# 3_RK.net
KiCad netlist of a schematic drawn in Altium Designer
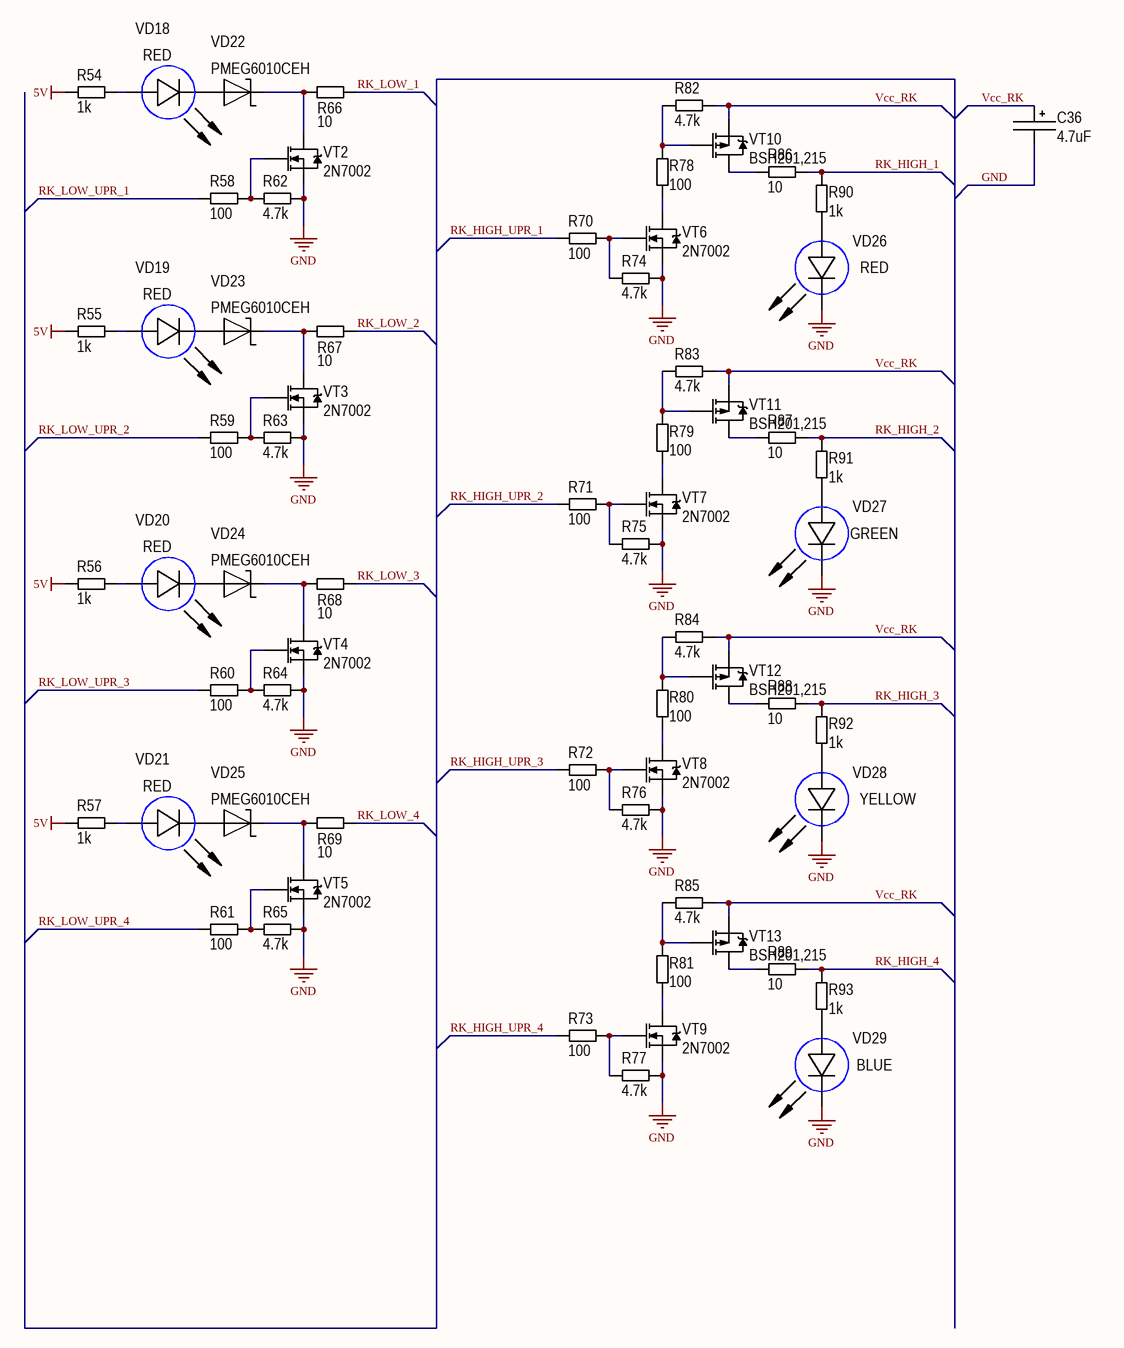
[diagram p0: 3_RK.SchDoc]

(export (version "E")
  (design (tool "Eeschema 10.0.6"))
  (components
    (comp (ref "C36")
      (value "4.7uF")
      (footprint "TANTAL_C")
      (libsource (lib "Condensators") (part "TantalCap"))
    )
    (comp (ref "R54") (value "1k") (footprint "CH0805R") (libsource (lib "Resistors") (part "Resistor")))
    (comp (ref "R55") (value "1k") (footprint "CH0805R") (libsource (lib "Resistors") (part "Resistor")))
    (comp (ref "R56") (value "1k") (footprint "CH0805R") (libsource (lib "Resistors") (part "Resistor")))
    (comp (ref "R57") (value "1k") (footprint "CH0805R") (libsource (lib "Resistors") (part "Resistor")))
    (comp (ref "R58") (value "100") (footprint "CH0603R") (libsource (lib "Resistors") (part "Resistor")))
    (comp (ref "R59") (value "100") (footprint "CH0603R") (libsource (lib "Resistors") (part "Resistor")))
    (comp (ref "R60") (value "100") (footprint "CH0603R") (libsource (lib "Resistors") (part "Resistor")))
    (comp (ref "R61") (value "100") (footprint "CH0603R") (libsource (lib "Resistors") (part "Resistor")))
    (comp (ref "R62") (value "4.7k") (footprint "CH0603R") (libsource (lib "Resistors") (part "Resistor")))
    (comp (ref "R63") (value "4.7k") (footprint "CH0603R") (libsource (lib "Resistors") (part "Resistor")))
    (comp (ref "R64") (value "4.7k") (footprint "CH0603R") (libsource (lib "Resistors") (part "Resistor")))
    (comp (ref "R65") (value "4.7k") (footprint "CH0603R") (libsource (lib "Resistors") (part "Resistor")))
    (comp (ref "R66") (value "10") (footprint "CH0603R") (libsource (lib "Resistors") (part "Resistor")))
    (comp (ref "R67") (value "10") (footprint "CH0603R") (libsource (lib "Resistors") (part "Resistor")))
    (comp (ref "R68") (value "10") (footprint "CH0603R") (libsource (lib "Resistors") (part "Resistor")))
    (comp (ref "R69") (value "10") (footprint "CH0603R") (libsource (lib "Resistors") (part "Resistor")))
    (comp (ref "R70") (value "100") (footprint "CH0603R") (libsource (lib "Resistors") (part "Resistor")))
    (comp (ref "R71") (value "100") (footprint "CH0603R") (libsource (lib "Resistors") (part "Resistor")))
    (comp (ref "R72") (value "100") (footprint "CH0603R") (libsource (lib "Resistors") (part "Resistor")))
    (comp (ref "R73") (value "100") (footprint "CH0603R") (libsource (lib "Resistors") (part "Resistor")))
    (comp (ref "R74") (value "4.7k") (footprint "CH0603R") (libsource (lib "Resistors") (part "Resistor")))
    (comp (ref "R75") (value "4.7k") (footprint "CH0603R") (libsource (lib "Resistors") (part "Resistor")))
    (comp (ref "R76") (value "4.7k") (footprint "CH0603R") (libsource (lib "Resistors") (part "Resistor")))
    (comp (ref "R77") (value "4.7k") (footprint "CH0603R") (libsource (lib "Resistors") (part "Resistor")))
    (comp (ref "R78") (value "100") (footprint "CH0603R") (libsource (lib "Resistors") (part "Resistor")))
    (comp (ref "R79") (value "100") (footprint "CH0603R") (libsource (lib "Resistors") (part "Resistor")))
    (comp (ref "R80") (value "100") (footprint "CH0603R") (libsource (lib "Resistors") (part "Resistor")))
    (comp (ref "R81") (value "100") (footprint "CH0603R") (libsource (lib "Resistors") (part "Resistor")))
    (comp (ref "R82") (value "4.7k") (footprint "CH0603R") (libsource (lib "Resistors") (part "Resistor")))
    (comp (ref "R83") (value "4.7k") (footprint "CH0603R") (libsource (lib "Resistors") (part "Resistor")))
    (comp (ref "R84") (value "4.7k") (footprint "CH0603R") (libsource (lib "Resistors") (part "Resistor")))
    (comp (ref "R85") (value "4.7k") (footprint "CH0603R") (libsource (lib "Resistors") (part "Resistor")))
    (comp (ref "R86") (value "10") (footprint "CH0603R") (libsource (lib "Resistors") (part "Resistor")))
    (comp (ref "R87") (value "10") (footprint "CH0603R") (libsource (lib "Resistors") (part "Resistor")))
    (comp (ref "R88") (value "10") (footprint "CH0603R") (libsource (lib "Resistors") (part "Resistor")))
    (comp (ref "R89") (value "10") (footprint "CH0603R") (libsource (lib "Resistors") (part "Resistor")))
    (comp (ref "R90") (value "1k") (footprint "CH0805R") (libsource (lib "Resistors") (part "Resistor")))
    (comp (ref "R91") (value "1k") (footprint "CH0805R") (libsource (lib "Resistors") (part "Resistor")))
    (comp (ref "R92") (value "1k") (footprint "CH0805R") (libsource (lib "Resistors") (part "Resistor")))
    (comp (ref "R93") (value "1k") (footprint "CH0805R") (libsource (lib "Resistors") (part "Resistor")))
    (comp (ref "VD18") (value "RED") (footprint "CH0603LB") (libsource (lib "Diods") (part "LED_1")))
    (comp (ref "VD19") (value "RED") (footprint "CH0603LB") (libsource (lib "Diods") (part "LED_1")))
    (comp (ref "VD20") (value "RED") (footprint "CH0603LB") (libsource (lib "Diods") (part "LED_1")))
    (comp (ref "VD21") (value "RED") (footprint "CH0603LB") (libsource (lib "Diods") (part "LED_1")))
    (comp (ref "VD22")
      (value "PMEG6010CEH")
      (footprint "SOD123F")
      (libsource (lib "Diods") (part "Diod Schottky"))
    )
    (comp (ref "VD23")
      (value "PMEG6010CEH")
      (footprint "SOD123F")
      (libsource (lib "Diods") (part "Diod Schottky"))
    )
    (comp (ref "VD24")
      (value "PMEG6010CEH")
      (footprint "SOD123F")
      (libsource (lib "Diods") (part "Diod Schottky"))
    )
    (comp (ref "VD25")
      (value "PMEG6010CEH")
      (footprint "SOD123F")
      (libsource (lib "Diods") (part "Diod Schottky"))
    )
    (comp (ref "VD26") (value "RED") (footprint "CH0603LB") (libsource (lib "Diods") (part "LED_1")))
    (comp (ref "VD27") (value "GREEN") (footprint "CH0603LB") (libsource (lib "Diods") (part "LED_1")))
    (comp (ref "VD28") (value "YELLOW") (footprint "CH0603LB") (libsource (lib "Diods") (part "LED_1")))
    (comp (ref "VD29") (value "BLUE") (footprint "CH0603LB") (libsource (lib "Diods") (part "LED_1")))
    (comp (ref "VT2")
      (value "2N7002")
      (footprint "SOT23_123")
      (description "Mosfet")
      (libsource (lib "Tranzistor") (part "N-chanel"))
    )
    (comp (ref "VT3")
      (value "2N7002")
      (footprint "SOT23_123")
      (description "Mosfet")
      (libsource (lib "Tranzistor") (part "N-chanel"))
    )
    (comp (ref "VT4")
      (value "2N7002")
      (footprint "SOT23_123")
      (description "Mosfet")
      (libsource (lib "Tranzistor") (part "N-chanel"))
    )
    (comp (ref "VT5")
      (value "2N7002")
      (footprint "SOT23_123")
      (description "Mosfet")
      (libsource (lib "Tranzistor") (part "N-chanel"))
    )
    (comp (ref "VT6")
      (value "2N7002")
      (footprint "SOT23_123")
      (description "Mosfet")
      (libsource (lib "Tranzistor") (part "N-chanel"))
    )
    (comp (ref "VT7")
      (value "2N7002")
      (footprint "SOT23_123")
      (description "Mosfet")
      (libsource (lib "Tranzistor") (part "N-chanel"))
    )
    (comp (ref "VT8")
      (value "2N7002")
      (footprint "SOT23_123")
      (description "Mosfet")
      (libsource (lib "Tranzistor") (part "N-chanel"))
    )
    (comp (ref "VT9")
      (value "2N7002")
      (footprint "SOT23_123")
      (description "Mosfet")
      (libsource (lib "Tranzistor") (part "N-chanel"))
    )
    (comp (ref "VT10")
      (value "BSH201,215")
      (footprint "SOT23_123")
      (description "Mosfet")
      (libsource (lib "Tranzistor") (part "P-chanel"))
    )
    (comp (ref "VT11")
      (value "BSH201,215")
      (footprint "SOT23_123")
      (description "Mosfet")
      (libsource (lib "Tranzistor") (part "P-chanel"))
    )
    (comp (ref "VT12")
      (value "BSH201,215")
      (footprint "SOT23_123")
      (description "Mosfet")
      (libsource (lib "Tranzistor") (part "P-chanel"))
    )
    (comp (ref "VT13")
      (value "BSH201,215")
      (footprint "SOT23_123")
      (description "Mosfet")
      (libsource (lib "Tranzistor") (part "P-chanel"))
    )
  )
  (nets
    (net (code "1") (name "/RK_HIGH_1") (class "Default")
      (node (ref "R86") (pin "1") (pinfunction "1_1") (pintype "passive"))
      (node (ref "R90") (pin "2") (pinfunction "2_2") (pintype "passive"))
    )
    (net (code "2") (name "/RK_HIGH_2") (class "Default")
      (node (ref "R87") (pin "1") (pinfunction "1_1") (pintype "passive"))
      (node (ref "R91") (pin "2") (pinfunction "2_2") (pintype "passive"))
    )
    (net (code "3") (name "/RK_HIGH_3") (class "Default")
      (node (ref "R88") (pin "1") (pinfunction "1_1") (pintype "passive"))
      (node (ref "R92") (pin "2") (pinfunction "2_2") (pintype "passive"))
    )
    (net (code "4") (name "/RK_HIGH_4") (class "Default")
      (node (ref "R89") (pin "1") (pinfunction "1_1") (pintype "passive"))
      (node (ref "R93") (pin "2") (pinfunction "2_2") (pintype "passive"))
    )
    (net (code "5") (name "/RK_HIGH_UPR_1") (class "Default")
      (node (ref "R70") (pin "2") (pinfunction "2_2") (pintype "passive"))
    )
    (net (code "6") (name "/RK_HIGH_UPR_2") (class "Default")
      (node (ref "R71") (pin "2") (pinfunction "2_2") (pintype "passive"))
    )
    (net (code "7") (name "/RK_HIGH_UPR_3") (class "Default")
      (node (ref "R72") (pin "2") (pinfunction "2_2") (pintype "passive"))
    )
    (net (code "8") (name "/RK_HIGH_UPR_4") (class "Default")
      (node (ref "R73") (pin "2") (pinfunction "2_2") (pintype "passive"))
    )
    (net (code "9") (name "/RK_LOW_1") (class "Default")
      (node (ref "R66") (pin "1") (pinfunction "1_1") (pintype "passive"))
    )
    (net (code "10") (name "/RK_LOW_2") (class "Default")
      (node (ref "R67") (pin "1") (pinfunction "1_1") (pintype "passive"))
    )
    (net (code "11") (name "/RK_LOW_3") (class "Default")
      (node (ref "R68") (pin "1") (pinfunction "1_1") (pintype "passive"))
    )
    (net (code "12") (name "/RK_LOW_4") (class "Default")
      (node (ref "R69") (pin "1") (pinfunction "1_1") (pintype "passive"))
    )
    (net (code "13") (name "/RK_LOW_UPR_1") (class "Default")
      (node (ref "R58") (pin "2") (pinfunction "2_2") (pintype "passive"))
    )
    (net (code "14") (name "/RK_LOW_UPR_2") (class "Default")
      (node (ref "R59") (pin "2") (pinfunction "2_2") (pintype "passive"))
    )
    (net (code "15") (name "/RK_LOW_UPR_3") (class "Default")
      (node (ref "R60") (pin "2") (pinfunction "2_2") (pintype "passive"))
    )
    (net (code "16") (name "/RK_LOW_UPR_4") (class "Default")
      (node (ref "R61") (pin "2") (pinfunction "2_2") (pintype "passive"))
    )
    (net (code "17") (name "/Vcc_RK") (class "Default")
      (node (ref "C36") (pin "1") (pinfunction "1_1") (pintype "power_in"))
      (node (ref "R82") (pin "1") (pinfunction "1_1") (pintype "passive"))
      (node (ref "R83") (pin "1") (pinfunction "1_1") (pintype "passive"))
      (node (ref "R84") (pin "1") (pinfunction "1_1") (pintype "passive"))
      (node (ref "R85") (pin "1") (pinfunction "1_1") (pintype "passive"))
      (node (ref "VT10") (pin "3") (pinfunction "S_3") (pintype "passive"))
      (node (ref "VT11") (pin "3") (pinfunction "S_3") (pintype "passive"))
      (node (ref "VT12") (pin "3") (pinfunction "S_3") (pintype "passive"))
      (node (ref "VT13") (pin "3") (pinfunction "S_3") (pintype "passive"))
    )
    (net (code "18") (name "5V") (class "Default")
      (node (ref "R54") (pin "2") (pinfunction "2_2") (pintype "passive"))
      (node (ref "R55") (pin "2") (pinfunction "2_2") (pintype "passive"))
      (node (ref "R56") (pin "2") (pinfunction "2_2") (pintype "passive"))
      (node (ref "R57") (pin "2") (pinfunction "2_2") (pintype "passive"))
    )
    (net (code "19") (name "GND") (class "Default")
      (node (ref "C36") (pin "2") (pinfunction "2_2") (pintype "power_in"))
      (node (ref "R62") (pin "1") (pinfunction "1_1") (pintype "passive"))
      (node (ref "R63") (pin "1") (pinfunction "1_1") (pintype "passive"))
      (node (ref "R64") (pin "1") (pinfunction "1_1") (pintype "passive"))
      (node (ref "R65") (pin "1") (pinfunction "1_1") (pintype "passive"))
      (node (ref "R74") (pin "1") (pinfunction "1_1") (pintype "passive"))
      (node (ref "R75") (pin "1") (pinfunction "1_1") (pintype "passive"))
      (node (ref "R76") (pin "1") (pinfunction "1_1") (pintype "passive"))
      (node (ref "R77") (pin "1") (pinfunction "1_1") (pintype "passive"))
      (node (ref "VD26") (pin "2") (pinfunction "C_2") (pintype "passive"))
      (node (ref "VD27") (pin "2") (pinfunction "C_2") (pintype "passive"))
      (node (ref "VD28") (pin "2") (pinfunction "C_2") (pintype "passive"))
      (node (ref "VD29") (pin "2") (pinfunction "C_2") (pintype "passive"))
      (node (ref "VT2") (pin "3") (pinfunction "S_3") (pintype "passive"))
      (node (ref "VT3") (pin "3") (pinfunction "S_3") (pintype "passive"))
      (node (ref "VT4") (pin "3") (pinfunction "S_3") (pintype "passive"))
      (node (ref "VT5") (pin "3") (pinfunction "S_3") (pintype "passive"))
      (node (ref "VT6") (pin "3") (pinfunction "S_3") (pintype "passive"))
      (node (ref "VT7") (pin "3") (pinfunction "S_3") (pintype "passive"))
      (node (ref "VT8") (pin "3") (pinfunction "S_3") (pintype "passive"))
      (node (ref "VT9") (pin "3") (pinfunction "S_3") (pintype "passive"))
    )
    (net (code "20") (name "Net-(VD18-A)") (class "Default")
      (node (ref "R54") (pin "1") (pinfunction "1_1") (pintype "passive"))
      (node (ref "VD18") (pin "1") (pinfunction "A_1") (pintype "passive"))
    )
    (net (code "21") (name "Net-(VD18-C)") (class "Default")
      (node (ref "VD18") (pin "2") (pinfunction "C_2") (pintype "passive"))
      (node (ref "VD22") (pin "1") (pinfunction "1_1") (pintype "passive"))
    )
    (net (code "22") (name "Net-(VD19-A)") (class "Default")
      (node (ref "R55") (pin "1") (pinfunction "1_1") (pintype "passive"))
      (node (ref "VD19") (pin "1") (pinfunction "A_1") (pintype "passive"))
    )
    (net (code "23") (name "Net-(VD19-C)") (class "Default")
      (node (ref "VD19") (pin "2") (pinfunction "C_2") (pintype "passive"))
      (node (ref "VD23") (pin "1") (pinfunction "1_1") (pintype "passive"))
    )
    (net (code "24") (name "Net-(VD20-A)") (class "Default")
      (node (ref "R56") (pin "1") (pinfunction "1_1") (pintype "passive"))
      (node (ref "VD20") (pin "1") (pinfunction "A_1") (pintype "passive"))
    )
    (net (code "25") (name "Net-(VD20-C)") (class "Default")
      (node (ref "VD20") (pin "2") (pinfunction "C_2") (pintype "passive"))
      (node (ref "VD24") (pin "1") (pinfunction "1_1") (pintype "passive"))
    )
    (net (code "26") (name "Net-(VD21-A)") (class "Default")
      (node (ref "R57") (pin "1") (pinfunction "1_1") (pintype "passive"))
      (node (ref "VD21") (pin "1") (pinfunction "A_1") (pintype "passive"))
    )
    (net (code "27") (name "Net-(VD21-C)") (class "Default")
      (node (ref "VD21") (pin "2") (pinfunction "C_2") (pintype "passive"))
      (node (ref "VD25") (pin "1") (pinfunction "1_1") (pintype "passive"))
    )
    (net (code "28") (name "Net-(VD26-A)") (class "Default")
      (node (ref "R90") (pin "1") (pinfunction "1_1") (pintype "passive"))
      (node (ref "VD26") (pin "1") (pinfunction "A_1") (pintype "passive"))
    )
    (net (code "29") (name "Net-(VD27-A)") (class "Default")
      (node (ref "R91") (pin "1") (pinfunction "1_1") (pintype "passive"))
      (node (ref "VD27") (pin "1") (pinfunction "A_1") (pintype "passive"))
    )
    (net (code "30") (name "Net-(VD28-A)") (class "Default")
      (node (ref "R92") (pin "1") (pinfunction "1_1") (pintype "passive"))
      (node (ref "VD28") (pin "1") (pinfunction "A_1") (pintype "passive"))
    )
    (net (code "31") (name "Net-(VD29-A)") (class "Default")
      (node (ref "R93") (pin "1") (pinfunction "1_1") (pintype "passive"))
      (node (ref "VD29") (pin "1") (pinfunction "A_1") (pintype "passive"))
    )
    (net (code "32") (name "Net-(VT2-D)") (class "Default")
      (node (ref "R66") (pin "2") (pinfunction "2_2") (pintype "passive"))
      (node (ref "VD22") (pin "2") (pinfunction "2_2") (pintype "passive"))
      (node (ref "VT2") (pin "2") (pinfunction "D_2") (pintype "passive"))
    )
    (net (code "33") (name "Net-(VT2-G)") (class "Default")
      (node (ref "R58") (pin "1") (pinfunction "1_1") (pintype "passive"))
      (node (ref "R62") (pin "2") (pinfunction "2_2") (pintype "passive"))
      (node (ref "VT2") (pin "1") (pinfunction "G_1") (pintype "passive"))
    )
    (net (code "34") (name "Net-(VT3-D)") (class "Default")
      (node (ref "R67") (pin "2") (pinfunction "2_2") (pintype "passive"))
      (node (ref "VD23") (pin "2") (pinfunction "2_2") (pintype "passive"))
      (node (ref "VT3") (pin "2") (pinfunction "D_2") (pintype "passive"))
    )
    (net (code "35") (name "Net-(VT3-G)") (class "Default")
      (node (ref "R59") (pin "1") (pinfunction "1_1") (pintype "passive"))
      (node (ref "R63") (pin "2") (pinfunction "2_2") (pintype "passive"))
      (node (ref "VT3") (pin "1") (pinfunction "G_1") (pintype "passive"))
    )
    (net (code "36") (name "Net-(VT4-D)") (class "Default")
      (node (ref "R68") (pin "2") (pinfunction "2_2") (pintype "passive"))
      (node (ref "VD24") (pin "2") (pinfunction "2_2") (pintype "passive"))
      (node (ref "VT4") (pin "2") (pinfunction "D_2") (pintype "passive"))
    )
    (net (code "37") (name "Net-(VT4-G)") (class "Default")
      (node (ref "R60") (pin "1") (pinfunction "1_1") (pintype "passive"))
      (node (ref "R64") (pin "2") (pinfunction "2_2") (pintype "passive"))
      (node (ref "VT4") (pin "1") (pinfunction "G_1") (pintype "passive"))
    )
    (net (code "38") (name "Net-(VT5-D)") (class "Default")
      (node (ref "R69") (pin "2") (pinfunction "2_2") (pintype "passive"))
      (node (ref "VD25") (pin "2") (pinfunction "2_2") (pintype "passive"))
      (node (ref "VT5") (pin "2") (pinfunction "D_2") (pintype "passive"))
    )
    (net (code "39") (name "Net-(VT5-G)") (class "Default")
      (node (ref "R61") (pin "1") (pinfunction "1_1") (pintype "passive"))
      (node (ref "R65") (pin "2") (pinfunction "2_2") (pintype "passive"))
      (node (ref "VT5") (pin "1") (pinfunction "G_1") (pintype "passive"))
    )
    (net (code "40") (name "Net-(VT6-D)") (class "Default")
      (node (ref "R78") (pin "2") (pinfunction "2_2") (pintype "passive"))
      (node (ref "VT6") (pin "2") (pinfunction "D_2") (pintype "passive"))
    )
    (net (code "41") (name "Net-(VT6-G)") (class "Default")
      (node (ref "R70") (pin "1") (pinfunction "1_1") (pintype "passive"))
      (node (ref "R74") (pin "2") (pinfunction "2_2") (pintype "passive"))
      (node (ref "VT6") (pin "1") (pinfunction "G_1") (pintype "passive"))
    )
    (net (code "42") (name "Net-(VT7-D)") (class "Default")
      (node (ref "R79") (pin "2") (pinfunction "2_2") (pintype "passive"))
      (node (ref "VT7") (pin "2") (pinfunction "D_2") (pintype "passive"))
    )
    (net (code "43") (name "Net-(VT7-G)") (class "Default")
      (node (ref "R71") (pin "1") (pinfunction "1_1") (pintype "passive"))
      (node (ref "R75") (pin "2") (pinfunction "2_2") (pintype "passive"))
      (node (ref "VT7") (pin "1") (pinfunction "G_1") (pintype "passive"))
    )
    (net (code "44") (name "Net-(VT8-D)") (class "Default")
      (node (ref "R80") (pin "2") (pinfunction "2_2") (pintype "passive"))
      (node (ref "VT8") (pin "2") (pinfunction "D_2") (pintype "passive"))
    )
    (net (code "45") (name "Net-(VT8-G)") (class "Default")
      (node (ref "R72") (pin "1") (pinfunction "1_1") (pintype "passive"))
      (node (ref "R76") (pin "2") (pinfunction "2_2") (pintype "passive"))
      (node (ref "VT8") (pin "1") (pinfunction "G_1") (pintype "passive"))
    )
    (net (code "46") (name "Net-(VT9-D)") (class "Default")
      (node (ref "R81") (pin "2") (pinfunction "2_2") (pintype "passive"))
      (node (ref "VT9") (pin "2") (pinfunction "D_2") (pintype "passive"))
    )
    (net (code "47") (name "Net-(VT9-G)") (class "Default")
      (node (ref "R73") (pin "1") (pinfunction "1_1") (pintype "passive"))
      (node (ref "R77") (pin "2") (pinfunction "2_2") (pintype "passive"))
      (node (ref "VT9") (pin "1") (pinfunction "G_1") (pintype "passive"))
    )
    (net (code "48") (name "Net-(VT10-D)") (class "Default")
      (node (ref "R86") (pin "2") (pinfunction "2_2") (pintype "passive"))
      (node (ref "VT10") (pin "2") (pinfunction "D_2") (pintype "passive"))
    )
    (net (code "49") (name "Net-(VT10-G)") (class "Default")
      (node (ref "R78") (pin "1") (pinfunction "1_1") (pintype "passive"))
      (node (ref "R82") (pin "2") (pinfunction "2_2") (pintype "passive"))
      (node (ref "VT10") (pin "1") (pinfunction "G_1") (pintype "passive"))
    )
    (net (code "50") (name "Net-(VT11-D)") (class "Default")
      (node (ref "R87") (pin "2") (pinfunction "2_2") (pintype "passive"))
      (node (ref "VT11") (pin "2") (pinfunction "D_2") (pintype "passive"))
    )
    (net (code "51") (name "Net-(VT11-G)") (class "Default")
      (node (ref "R79") (pin "1") (pinfunction "1_1") (pintype "passive"))
      (node (ref "R83") (pin "2") (pinfunction "2_2") (pintype "passive"))
      (node (ref "VT11") (pin "1") (pinfunction "G_1") (pintype "passive"))
    )
    (net (code "52") (name "Net-(VT12-D)") (class "Default")
      (node (ref "R88") (pin "2") (pinfunction "2_2") (pintype "passive"))
      (node (ref "VT12") (pin "2") (pinfunction "D_2") (pintype "passive"))
    )
    (net (code "53") (name "Net-(VT12-G)") (class "Default")
      (node (ref "R80") (pin "1") (pinfunction "1_1") (pintype "passive"))
      (node (ref "R84") (pin "2") (pinfunction "2_2") (pintype "passive"))
      (node (ref "VT12") (pin "1") (pinfunction "G_1") (pintype "passive"))
    )
    (net (code "54") (name "Net-(VT13-D)") (class "Default")
      (node (ref "R89") (pin "2") (pinfunction "2_2") (pintype "passive"))
      (node (ref "VT13") (pin "2") (pinfunction "D_2") (pintype "passive"))
    )
    (net (code "55") (name "Net-(VT13-G)") (class "Default")
      (node (ref "R81") (pin "1") (pinfunction "1_1") (pintype "passive"))
      (node (ref "R85") (pin "2") (pinfunction "2_2") (pintype "passive"))
      (node (ref "VT13") (pin "1") (pinfunction "G_1") (pintype "passive"))
    )
  )
)
